# flash.net
KiCad netlist of a schematic drawn in Altium Designer
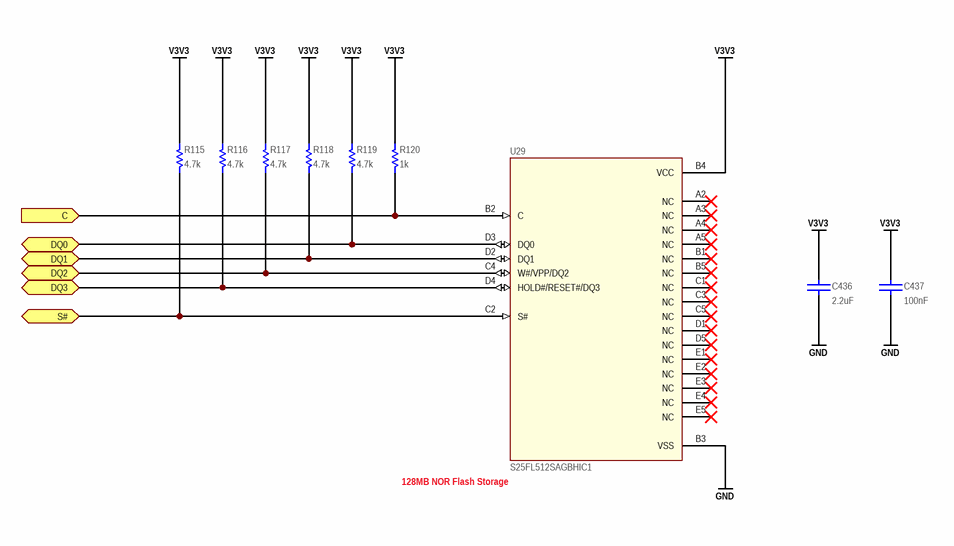
[diagram p0: flash.SchDoc]

(export (version "E")
  (design (tool "Eeschema 10.0.6"))
  (components
    (comp (ref "C436")
      (value "2.2uF")
      (footprint "CAPC160X80X90L20N")
      (description "Ceramic Capacitor 2.2uF ±20% 10V X7R 0603")
      (fields (field (name "MANUFACTURER") "TDK") (field (name "TOLERANCE") "±20%"))
      (libsource (lib "generic") (part "CAP"))
    )
    (comp (ref "C437")
      (value "100nF")
      (footprint "CAPC100X50X55L25N")
      (description "Ceramic Capacitor 100nF ±10% 50V X7R 0402")
      (fields (field (name "MANUFACTURER") "Murata") (field (name "TOLERANCE") "±10%"))
      (libsource (lib "generic") (part "CAP"))
    )
    (comp (ref "R115")
      (value "4.7k")
      (footprint "RESC1005X40N")
      (description "Thick Film Resistor 4.7k ±1% 0.1W 75V 0402")
      (fields (field (name "TOLERANCE") "±1%") (field (name "MANUFACTURER") "Panasonic"))
      (libsource (lib "generic") (part "RES"))
    )
    (comp (ref "R116")
      (value "4.7k")
      (footprint "RESC1005X40N")
      (description "Thick Film Resistor 4.7k ±1% 0.1W 75V 0402")
      (fields (field (name "TOLERANCE") "±1%") (field (name "MANUFACTURER") "Panasonic"))
      (libsource (lib "generic") (part "RES"))
    )
    (comp (ref "R117")
      (value "4.7k")
      (footprint "RESC1005X40N")
      (description "Thick Film Resistor 4.7k ±1% 0.1W 75V 0402")
      (fields (field (name "TOLERANCE") "±1%") (field (name "MANUFACTURER") "Panasonic"))
      (libsource (lib "generic") (part "RES"))
    )
    (comp (ref "R118")
      (value "4.7k")
      (footprint "RESC1005X40N")
      (description "Thick Film Resistor 4.7k ±1% 0.1W 75V 0402")
      (fields (field (name "TOLERANCE") "±1%") (field (name "MANUFACTURER") "Panasonic"))
      (libsource (lib "generic") (part "RES"))
    )
    (comp (ref "R119")
      (value "4.7k")
      (footprint "RESC1005X40N")
      (description "Thick Film Resistor 4.7k ±1% 0.1W 75V 0402")
      (fields (field (name "TOLERANCE") "±1%") (field (name "MANUFACTURER") "Panasonic"))
      (libsource (lib "generic") (part "RES"))
    )
    (comp (ref "R120")
      (value "1k")
      (footprint "RESC1005X40N")
      (description "Thick Film Resistor 1k ±1% 0.1W 50V 0402")
      (fields (field (name "TOLERANCE") "±1%") (field (name "MANUFACTURER") "Panasonic"))
      (libsource (lib "generic") (part "RES"))
    )
    (comp (ref "U29")
      (value "S25FL512SAGBHIC1")
      (footprint "micron:L-PBGA-24")
      (description "1024Mb, 3.3V Serial Flash Memory LBGA24")
      (fields (field (name "MANUFACTURER") "Cypress"))
      (libsource (lib "micron") (part "N25Q00AA13G1240"))
    )
  )
  (nets
    (net (code "1") (name "/C") (class "Default")
      (node (ref "R120") (pin "1") (pinfunction "1_1") (pintype "passive"))
      (node (ref "U29") (pin "B2") (pinfunction "C_B2") (pintype "input"))
    )
    (net (code "2") (name "/DQ0") (class "Default")
      (node (ref "R119") (pin "1") (pinfunction "1_1") (pintype "passive"))
      (node (ref "U29") (pin "D3") (pinfunction "DQ0_D3") (pintype "bidirectional"))
    )
    (net (code "3") (name "/DQ1") (class "Default")
      (node (ref "R118") (pin "1") (pinfunction "1_1") (pintype "passive"))
      (node (ref "U29") (pin "D2") (pinfunction "DQ1_D2") (pintype "bidirectional"))
    )
    (net (code "4") (name "/DQ2") (class "Default")
      (node (ref "R117") (pin "1") (pinfunction "1_1") (pintype "passive"))
      (node (ref "U29") (pin "C4") (pinfunction "W#/VPP/DQ2_C4") (pintype "bidirectional"))
    )
    (net (code "5") (name "/DQ3") (class "Default")
      (node (ref "R116") (pin "1") (pinfunction "1_1") (pintype "passive"))
      (node (ref "U29") (pin "D4") (pinfunction "HOLD#/RESET#/DQ3_D4") (pintype "bidirectional"))
    )
    (net (code "6") (name "/S#") (class "Default")
      (node (ref "R115") (pin "1") (pinfunction "1_1") (pintype "passive"))
      (node (ref "U29") (pin "C2") (pinfunction "S#_C2") (pintype "input"))
    )
    (net (code "7") (name "GND") (class "Default")
      (node (ref "C436") (pin "1") (pinfunction "1_1") (pintype "passive"))
      (node (ref "C437") (pin "1") (pinfunction "1_1") (pintype "passive"))
      (node (ref "U29") (pin "B3") (pinfunction "VSS_B3") (pintype "power_in"))
    )
    (net (code "8") (name "V3V3") (class "Default")
      (node (ref "C436") (pin "2") (pinfunction "2_2") (pintype "passive"))
      (node (ref "C437") (pin "2") (pinfunction "2_2") (pintype "passive"))
      (node (ref "R115") (pin "2") (pinfunction "2_2") (pintype "passive"))
      (node (ref "R116") (pin "2") (pinfunction "2_2") (pintype "passive"))
      (node (ref "R117") (pin "2") (pinfunction "2_2") (pintype "passive"))
      (node (ref "R118") (pin "2") (pinfunction "2_2") (pintype "passive"))
      (node (ref "R119") (pin "2") (pinfunction "2_2") (pintype "passive"))
      (node (ref "R120") (pin "2") (pinfunction "2_2") (pintype "passive"))
      (node (ref "U29") (pin "B4") (pinfunction "VCC_B4") (pintype "power_in"))
    )
    (net (code "9") (name "unconnected-(U29-NC-PadA2)") (class "Default")
      (node (ref "U29") (pin "A2") (pinfunction "NC_A2") (pintype "passive+no_connect"))
    )
    (net (code "10") (name "unconnected-(U29-NC-PadA3)") (class "Default")
      (node (ref "U29") (pin "A3") (pinfunction "NC_A3") (pintype "passive+no_connect"))
    )
    (net (code "11") (name "unconnected-(U29-NC-PadA4)") (class "Default")
      (node (ref "U29") (pin "A4") (pinfunction "NC_A4") (pintype "passive+no_connect"))
    )
    (net (code "12") (name "unconnected-(U29-NC-PadA5)") (class "Default")
      (node (ref "U29") (pin "A5") (pinfunction "NC_A5") (pintype "passive+no_connect"))
    )
    (net (code "13") (name "unconnected-(U29-NC-PadB1)") (class "Default")
      (node (ref "U29") (pin "B1") (pinfunction "NC_B1") (pintype "passive+no_connect"))
    )
    (net (code "14") (name "unconnected-(U29-NC-PadB5)") (class "Default")
      (node (ref "U29") (pin "B5") (pinfunction "NC_B5") (pintype "passive+no_connect"))
    )
    (net (code "15") (name "unconnected-(U29-NC-PadC1)") (class "Default")
      (node (ref "U29") (pin "C1") (pinfunction "NC_C1") (pintype "passive+no_connect"))
    )
    (net (code "16") (name "unconnected-(U29-NC-PadC3)") (class "Default")
      (node (ref "U29") (pin "C3") (pinfunction "NC_C3") (pintype "passive+no_connect"))
    )
    (net (code "17") (name "unconnected-(U29-NC-PadC5)") (class "Default")
      (node (ref "U29") (pin "C5") (pinfunction "NC_C5") (pintype "passive+no_connect"))
    )
    (net (code "18") (name "unconnected-(U29-NC-PadD1)") (class "Default")
      (node (ref "U29") (pin "D1") (pinfunction "NC_D1") (pintype "passive+no_connect"))
    )
    (net (code "19") (name "unconnected-(U29-NC-PadD5)") (class "Default")
      (node (ref "U29") (pin "D5") (pinfunction "NC_D5") (pintype "passive+no_connect"))
    )
    (net (code "20") (name "unconnected-(U29-NC-PadE1)") (class "Default")
      (node (ref "U29") (pin "E1") (pinfunction "NC_E1") (pintype "passive+no_connect"))
    )
    (net (code "21") (name "unconnected-(U29-NC-PadE2)") (class "Default")
      (node (ref "U29") (pin "E2") (pinfunction "NC_E2") (pintype "passive+no_connect"))
    )
    (net (code "22") (name "unconnected-(U29-NC-PadE3)") (class "Default")
      (node (ref "U29") (pin "E3") (pinfunction "NC_E3") (pintype "passive+no_connect"))
    )
    (net (code "23") (name "unconnected-(U29-NC-PadE4)") (class "Default")
      (node (ref "U29") (pin "E4") (pinfunction "NC_E4") (pintype "passive+no_connect"))
    )
    (net (code "24") (name "unconnected-(U29-NC-PadE5)") (class "Default")
      (node (ref "U29") (pin "E5") (pinfunction "NC_E5") (pintype "passive+no_connect"))
    )
  )
)
